# motherboard.net
KiCad netlist of a schematic drawn in EAGLE
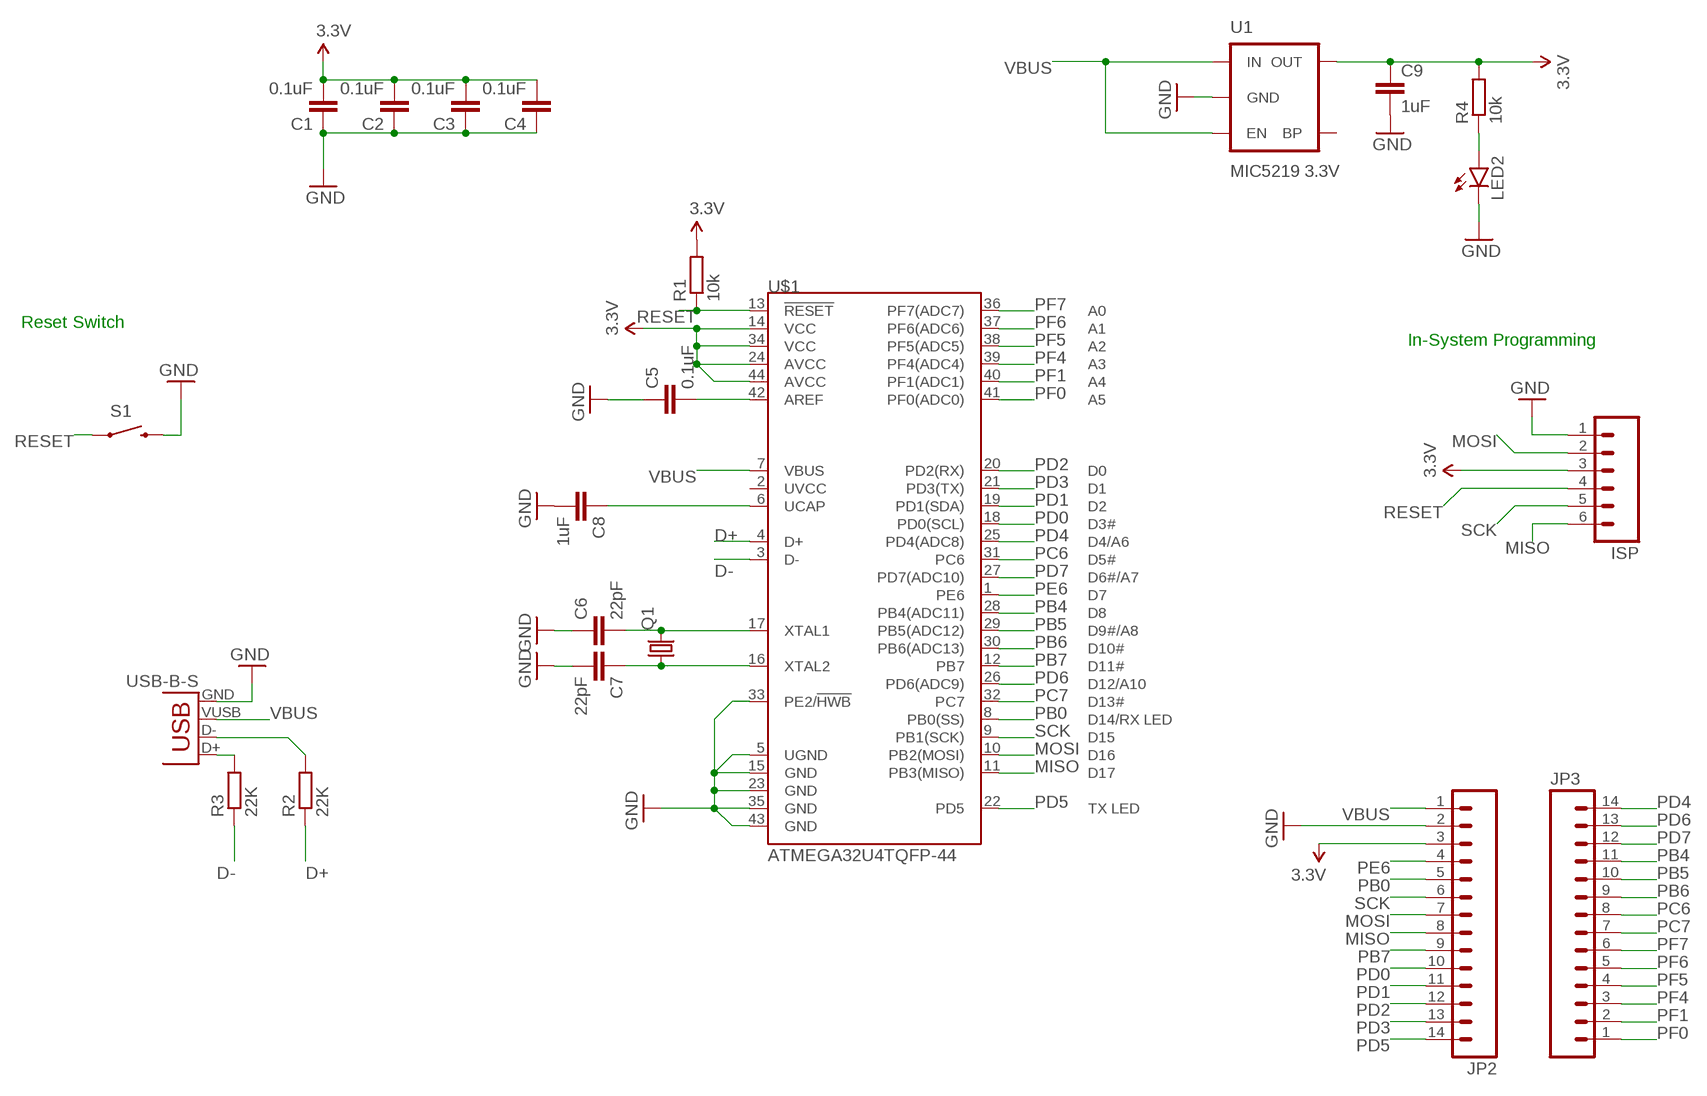
[diagram p0: schematic, sheet 1]

(export (version "E")
  (design (tool "Eeschema 10.0.6"))
  (components
    (comp (ref "C1")
      (value "0.1uF")
      (footprint "eagle-import:C0805")
      (libsource (lib "eagle-import") (part "C0805"))
    )
    (comp (ref "C2")
      (value "0.1uF")
      (footprint "eagle-import:C0805")
      (libsource (lib "eagle-import") (part "C0805"))
    )
    (comp (ref "C3")
      (value "0.1uF")
      (footprint "eagle-import:C0805")
      (libsource (lib "eagle-import") (part "C0805"))
    )
    (comp (ref "C4")
      (value "0.1uF")
      (footprint "eagle-import:C0805")
      (libsource (lib "eagle-import") (part "C0805"))
    )
    (comp (ref "C5")
      (value "0.1uF")
      (footprint "eagle-import:C0805")
      (libsource (lib "eagle-import") (part "C0805"))
    )
    (comp (ref "C6")
      (value "22pF")
      (footprint "eagle-import:C0805")
      (libsource (lib "eagle-import") (part "C0805"))
    )
    (comp (ref "C7")
      (value "22pF")
      (footprint "eagle-import:C0805")
      (libsource (lib "eagle-import") (part "C0805"))
    )
    (comp (ref "C8")
      (value "1uF")
      (footprint "eagle-import:C0805")
      (libsource (lib "eagle-import") (part "C0805"))
    )
    (comp (ref "C9")
      (value "1uF")
      (footprint "eagle-import:C0805")
      (libsource (lib "eagle-import") (part "C0805"))
    )
    (comp (ref "ISP")
      (value "M06SMD")
      (footprint "eagle-import:1X06-SMD")
      (libsource (lib "eagle-import") (part "M06SMD"))
    )
    (comp (ref "JP1")
      (value "USB-B-S")
      (footprint "eagle-import:USB-B-SMT")
      (libsource (lib "eagle-import") (part "USB-B-S"))
    )
    (comp (ref "JP2")
      (value "M14")
      (footprint "eagle-import:1X14")
      (libsource (lib "eagle-import") (part "M14"))
    )
    (comp (ref "JP3")
      (value "M14")
      (footprint "eagle-import:1X14")
      (libsource (lib "eagle-import") (part "M14"))
    )
    (comp (ref "LED2")
      (value "LED1206")
      (footprint "eagle-import:LED-1206")
      (libsource (lib "eagle-import") (part "LED1206"))
    )
    (comp (ref "Q1")
      (value "CRYSTALHC49S")
      (footprint "eagle-import:HC49_S")
      (libsource (lib "eagle-import") (part "CRYSTALHC49S"))
    )
    (comp (ref "R1")
      (value "10k")
      (footprint "eagle-import:R0805")
      (libsource (lib "eagle-import") (part "R0805"))
    )
    (comp (ref "R2")
      (value "22K")
      (footprint "eagle-import:R0805")
      (libsource (lib "eagle-import") (part "R0805"))
    )
    (comp (ref "R3")
      (value "22K")
      (footprint "eagle-import:R0805")
      (libsource (lib "eagle-import") (part "R0805"))
    )
    (comp (ref "R4")
      (value "10k")
      (footprint "eagle-import:R0805")
      (libsource (lib "eagle-import") (part "R0805"))
    )
    (comp (ref "S1")
      (value "SWITCH-MOMENTARY-2PTH")
      (footprint "eagle-import:TACTILE-PTH")
      (libsource (lib "eagle-import") (part "SWITCH-MOMENTARY-2PTH"))
    )
    (comp (ref "U$1")
      (value "ATMEGA32U4TQFP-44")
      (footprint "eagle-import:TQFP44")
      (libsource (lib "eagle-import") (part "ATMEGA32U4TQFP-44"))
    )
    (comp (ref "U1")
      (value "MIC5219 3.3V")
      (footprint "eagle-import:SOT23-5")
      (libsource (lib "eagle-import") (part "V_REG_MIC52193.3V"))
    )
  )
  (nets
    (net (code "1") (name "/D+") (class "Default")
      (node (ref "R2") (pin "1") (pinfunction "1_1") (pintype "passive"))
      (node (ref "U$1") (pin "4") (pinfunction "D+_4") (pintype "bidirectional"))
    )
    (net (code "2") (name "/D-") (class "Default")
      (node (ref "R3") (pin "1") (pinfunction "1_1") (pintype "passive"))
      (node (ref "U$1") (pin "3") (pinfunction "D-_3") (pintype "bidirectional"))
    )
    (net (code "3") (name "/MISO") (class "Default")
      (node (ref "ISP") (pin "6") (pinfunction "6_6") (pintype "passive"))
      (node (ref "JP2") (pin "8") (pinfunction "8_8") (pintype "passive"))
      (node (ref "U$1") (pin "11") (pinfunction "PB3(MISO)_11") (pintype "bidirectional"))
    )
    (net (code "4") (name "/MOSI") (class "Default")
      (node (ref "ISP") (pin "2") (pinfunction "2_2") (pintype "passive"))
      (node (ref "JP2") (pin "7") (pinfunction "7_7") (pintype "passive"))
      (node (ref "U$1") (pin "10") (pinfunction "PB2(MOSI)_10") (pintype "bidirectional"))
    )
    (net (code "5") (name "/PB0") (class "Default")
      (node (ref "JP2") (pin "5") (pinfunction "5_5") (pintype "passive"))
      (node (ref "U$1") (pin "8") (pinfunction "PB0(SS)_8") (pintype "bidirectional"))
    )
    (net (code "6") (name "/PB4") (class "Default")
      (node (ref "JP3") (pin "11") (pinfunction "11_11") (pintype "passive"))
      (node (ref "U$1") (pin "28") (pinfunction "PB4(ADC11)_28") (pintype "bidirectional"))
    )
    (net (code "7") (name "/PB5") (class "Default")
      (node (ref "JP3") (pin "10") (pinfunction "10_10") (pintype "passive"))
      (node (ref "U$1") (pin "29") (pinfunction "PB5(ADC12)_29") (pintype "bidirectional"))
    )
    (net (code "8") (name "/PB6") (class "Default")
      (node (ref "JP3") (pin "9") (pinfunction "9_9") (pintype "passive"))
      (node (ref "U$1") (pin "30") (pinfunction "PB6(ADC13)_30") (pintype "bidirectional"))
    )
    (net (code "9") (name "/PB7") (class "Default")
      (node (ref "JP2") (pin "9") (pinfunction "9_9") (pintype "passive"))
      (node (ref "U$1") (pin "12") (pinfunction "PB7_12") (pintype "bidirectional"))
    )
    (net (code "10") (name "/PC6") (class "Default")
      (node (ref "JP3") (pin "8") (pinfunction "8_8") (pintype "passive"))
      (node (ref "U$1") (pin "31") (pinfunction "PC6_31") (pintype "bidirectional"))
    )
    (net (code "11") (name "/PC7") (class "Default")
      (node (ref "JP3") (pin "7") (pinfunction "7_7") (pintype "passive"))
      (node (ref "U$1") (pin "32") (pinfunction "PC7_32") (pintype "bidirectional"))
    )
    (net (code "12") (name "/PD0") (class "Default")
      (node (ref "JP2") (pin "10") (pinfunction "10_10") (pintype "passive"))
      (node (ref "U$1") (pin "18") (pinfunction "PD0(SCL)_18") (pintype "bidirectional"))
    )
    (net (code "13") (name "/PD1") (class "Default")
      (node (ref "JP2") (pin "11") (pinfunction "11_11") (pintype "passive"))
      (node (ref "U$1") (pin "19") (pinfunction "PD1(SDA)_19") (pintype "bidirectional"))
    )
    (net (code "14") (name "/PD2") (class "Default")
      (node (ref "JP2") (pin "12") (pinfunction "12_12") (pintype "passive"))
      (node (ref "U$1") (pin "20") (pinfunction "PD2(RX)_20") (pintype "bidirectional"))
    )
    (net (code "15") (name "/PD3") (class "Default")
      (node (ref "JP2") (pin "13") (pinfunction "13_13") (pintype "passive"))
      (node (ref "U$1") (pin "21") (pinfunction "PD3(TX)_21") (pintype "bidirectional"))
    )
    (net (code "16") (name "/PD4") (class "Default")
      (node (ref "JP3") (pin "14") (pinfunction "14_14") (pintype "passive"))
      (node (ref "U$1") (pin "25") (pinfunction "PD4(ADC8)_25") (pintype "bidirectional"))
    )
    (net (code "17") (name "/PD5") (class "Default")
      (node (ref "JP2") (pin "14") (pinfunction "14_14") (pintype "passive"))
      (node (ref "U$1") (pin "22") (pinfunction "PD5_22") (pintype "bidirectional"))
    )
    (net (code "18") (name "/PD6") (class "Default")
      (node (ref "JP3") (pin "13") (pinfunction "13_13") (pintype "passive"))
      (node (ref "U$1") (pin "26") (pinfunction "PD6(ADC9)_26") (pintype "bidirectional"))
    )
    (net (code "19") (name "/PD7") (class "Default")
      (node (ref "JP3") (pin "12") (pinfunction "12_12") (pintype "passive"))
      (node (ref "U$1") (pin "27") (pinfunction "PD7(ADC10)_27") (pintype "bidirectional"))
    )
    (net (code "20") (name "/PE6") (class "Default")
      (node (ref "JP2") (pin "4") (pinfunction "4_4") (pintype "passive"))
      (node (ref "U$1") (pin "1") (pinfunction "PE6_1") (pintype "bidirectional"))
    )
    (net (code "21") (name "/PF0") (class "Default")
      (node (ref "JP3") (pin "1") (pinfunction "1_1") (pintype "passive"))
      (node (ref "U$1") (pin "41") (pinfunction "PF0(ADC0)_41") (pintype "bidirectional"))
    )
    (net (code "22") (name "/PF1") (class "Default")
      (node (ref "JP3") (pin "2") (pinfunction "2_2") (pintype "passive"))
      (node (ref "U$1") (pin "40") (pinfunction "PF1(ADC1)_40") (pintype "bidirectional"))
    )
    (net (code "23") (name "/PF4") (class "Default")
      (node (ref "JP3") (pin "3") (pinfunction "3_3") (pintype "passive"))
      (node (ref "U$1") (pin "39") (pinfunction "PF4(ADC4)_39") (pintype "bidirectional"))
    )
    (net (code "24") (name "/PF5") (class "Default")
      (node (ref "JP3") (pin "4") (pinfunction "4_4") (pintype "passive"))
      (node (ref "U$1") (pin "38") (pinfunction "PF5(ADC5)_38") (pintype "bidirectional"))
    )
    (net (code "25") (name "/PF6") (class "Default")
      (node (ref "JP3") (pin "5") (pinfunction "5_5") (pintype "passive"))
      (node (ref "U$1") (pin "37") (pinfunction "PF6(ADC6)_37") (pintype "bidirectional"))
    )
    (net (code "26") (name "/PF7") (class "Default")
      (node (ref "JP3") (pin "6") (pinfunction "6_6") (pintype "passive"))
      (node (ref "U$1") (pin "36") (pinfunction "PF7(ADC7)_36") (pintype "bidirectional"))
    )
    (net (code "27") (name "/RESET") (class "Default")
      (node (ref "ISP") (pin "4") (pinfunction "4_4") (pintype "passive"))
      (node (ref "R1") (pin "1") (pinfunction "1_1") (pintype "passive"))
      (node (ref "S1") (pin "1") (pinfunction "1_1") (pintype "passive"))
      (node (ref "U$1") (pin "13") (pinfunction "~{RESET}_13") (pintype "bidirectional"))
    )
    (net (code "28") (name "/SCK") (class "Default")
      (node (ref "ISP") (pin "5") (pinfunction "5_5") (pintype "passive"))
      (node (ref "JP2") (pin "6") (pinfunction "6_6") (pintype "passive"))
      (node (ref "U$1") (pin "9") (pinfunction "PB1(SCK)_9") (pintype "bidirectional"))
    )
    (net (code "29") (name "/VBUS") (class "Default")
      (node (ref "JP1") (pin "VUSB") (pinfunction "VBUS_VUSB") (pintype "bidirectional"))
      (node (ref "JP2") (pin "1") (pinfunction "1_1") (pintype "passive"))
      (node (ref "U$1") (pin "7") (pinfunction "VBUS_7") (pintype "bidirectional"))
      (node (ref "U1") (pin "1") (pinfunction "IN_1") (pintype "input"))
      (node (ref "U1") (pin "3") (pinfunction "EN_3") (pintype "input"))
    )
    (net (code "30") (name "3.3V") (class "Default")
      (node (ref "C1") (pin "2") (pinfunction "2_2") (pintype "passive"))
      (node (ref "C2") (pin "2") (pinfunction "2_2") (pintype "passive"))
      (node (ref "C3") (pin "2") (pinfunction "2_2") (pintype "passive"))
      (node (ref "C4") (pin "2") (pinfunction "2_2") (pintype "passive"))
      (node (ref "C9") (pin "1") (pinfunction "1_1") (pintype "passive"))
      (node (ref "ISP") (pin "3") (pinfunction "3_3") (pintype "passive"))
      (node (ref "JP2") (pin "3") (pinfunction "3_3") (pintype "passive"))
      (node (ref "R1") (pin "2") (pinfunction "2_2") (pintype "passive"))
      (node (ref "R4") (pin "2") (pinfunction "2_2") (pintype "passive"))
      (node (ref "U$1") (pin "14") (pinfunction "VCC_14") (pintype "bidirectional"))
      (node (ref "U$1") (pin "24") (pinfunction "AVCC_24") (pintype "bidirectional"))
      (node (ref "U$1") (pin "34") (pinfunction "VCC_34") (pintype "bidirectional"))
      (node (ref "U$1") (pin "44") (pinfunction "AVCC_44") (pintype "bidirectional"))
      (node (ref "U1") (pin "5") (pinfunction "OUT_5") (pintype "passive"))
    )
    (net (code "31") (name "GND") (class "Default")
      (node (ref "C1") (pin "1") (pinfunction "1_1") (pintype "passive"))
      (node (ref "C2") (pin "1") (pinfunction "1_1") (pintype "passive"))
      (node (ref "C3") (pin "1") (pinfunction "1_1") (pintype "passive"))
      (node (ref "C4") (pin "1") (pinfunction "1_1") (pintype "passive"))
      (node (ref "C5") (pin "1") (pinfunction "1_1") (pintype "passive"))
      (node (ref "C6") (pin "1") (pinfunction "1_1") (pintype "passive"))
      (node (ref "C7") (pin "2") (pinfunction "2_2") (pintype "passive"))
      (node (ref "C8") (pin "2") (pinfunction "2_2") (pintype "passive"))
      (node (ref "C9") (pin "2") (pinfunction "2_2") (pintype "passive"))
      (node (ref "ISP") (pin "1") (pinfunction "1_1") (pintype "passive"))
      (node (ref "JP1") (pin "GND") (pinfunction "GND_GND") (pintype "bidirectional"))
      (node (ref "JP2") (pin "2") (pinfunction "2_2") (pintype "passive"))
      (node (ref "LED2") (pin "C") (pinfunction "C_C") (pintype "passive"))
      (node (ref "S1") (pin "3") (pinfunction "2_3") (pintype "passive"))
      (node (ref "U$1") (pin "15") (pinfunction "GND_15") (pintype "bidirectional"))
      (node (ref "U$1") (pin "23") (pinfunction "GND_23") (pintype "bidirectional"))
      (node (ref "U$1") (pin "33") (pinfunction "PE2/~{HWB}_33") (pintype "bidirectional"))
      (node (ref "U$1") (pin "35") (pinfunction "GND_35") (pintype "bidirectional"))
      (node (ref "U$1") (pin "43") (pinfunction "GND_43") (pintype "bidirectional"))
      (node (ref "U$1") (pin "5") (pinfunction "UGND_5") (pintype "bidirectional"))
      (node (ref "U1") (pin "2") (pinfunction "GND_2") (pintype "input"))
    )
    (net (code "32") (name "Net-(JP1-PadD+)") (class "Default")
      (node (ref "JP1") (pin "D+") (pinfunction "D+_D+") (pintype "bidirectional"))
      (node (ref "R3") (pin "2") (pinfunction "2_2") (pintype "passive"))
    )
    (net (code "33") (name "Net-(JP1-PadD-)") (class "Default")
      (node (ref "JP1") (pin "D-") (pinfunction "D-_D-") (pintype "bidirectional"))
      (node (ref "R2") (pin "2") (pinfunction "2_2") (pintype "passive"))
    )
    (net (code "34") (name "Net-(LED2-PadA)") (class "Default")
      (node (ref "LED2") (pin "A") (pinfunction "A_A") (pintype "passive"))
      (node (ref "R4") (pin "1") (pinfunction "1_1") (pintype "passive"))
    )
    (net (code "35") (name "Net-(U$1-AREF)") (class "Default")
      (node (ref "C5") (pin "2") (pinfunction "2_2") (pintype "passive"))
      (node (ref "U$1") (pin "42") (pinfunction "AREF_42") (pintype "bidirectional"))
    )
    (net (code "36") (name "Net-(U$1-UCAP)") (class "Default")
      (node (ref "C8") (pin "1") (pinfunction "1_1") (pintype "passive"))
      (node (ref "U$1") (pin "6") (pinfunction "UCAP_6") (pintype "bidirectional"))
    )
    (net (code "37") (name "Net-(U$1-XTAL1)") (class "Default")
      (node (ref "C6") (pin "2") (pinfunction "2_2") (pintype "passive"))
      (node (ref "Q1") (pin "2") (pinfunction "2_2") (pintype "passive"))
      (node (ref "U$1") (pin "17") (pinfunction "XTAL1_17") (pintype "bidirectional"))
    )
    (net (code "38") (name "Net-(U$1-XTAL2)") (class "Default")
      (node (ref "C7") (pin "1") (pinfunction "1_1") (pintype "passive"))
      (node (ref "Q1") (pin "1") (pinfunction "1_1") (pintype "passive"))
      (node (ref "U$1") (pin "16") (pinfunction "XTAL2_16") (pintype "bidirectional"))
    )
    (net (code "39") (name "unconnected-(U$1-UVCC-Pad2)") (class "Default")
      (node (ref "U$1") (pin "2") (pinfunction "UVCC_2") (pintype "bidirectional"))
    )
    (net (code "40") (name "unconnected-(U1-BP-Pad4)") (class "Default")
      (node (ref "U1") (pin "4") (pinfunction "BP_4") (pintype "input"))
    )
  )
)
